# aepro_27C512.net
KiCad netlist of a schematic drawn in EAGLE
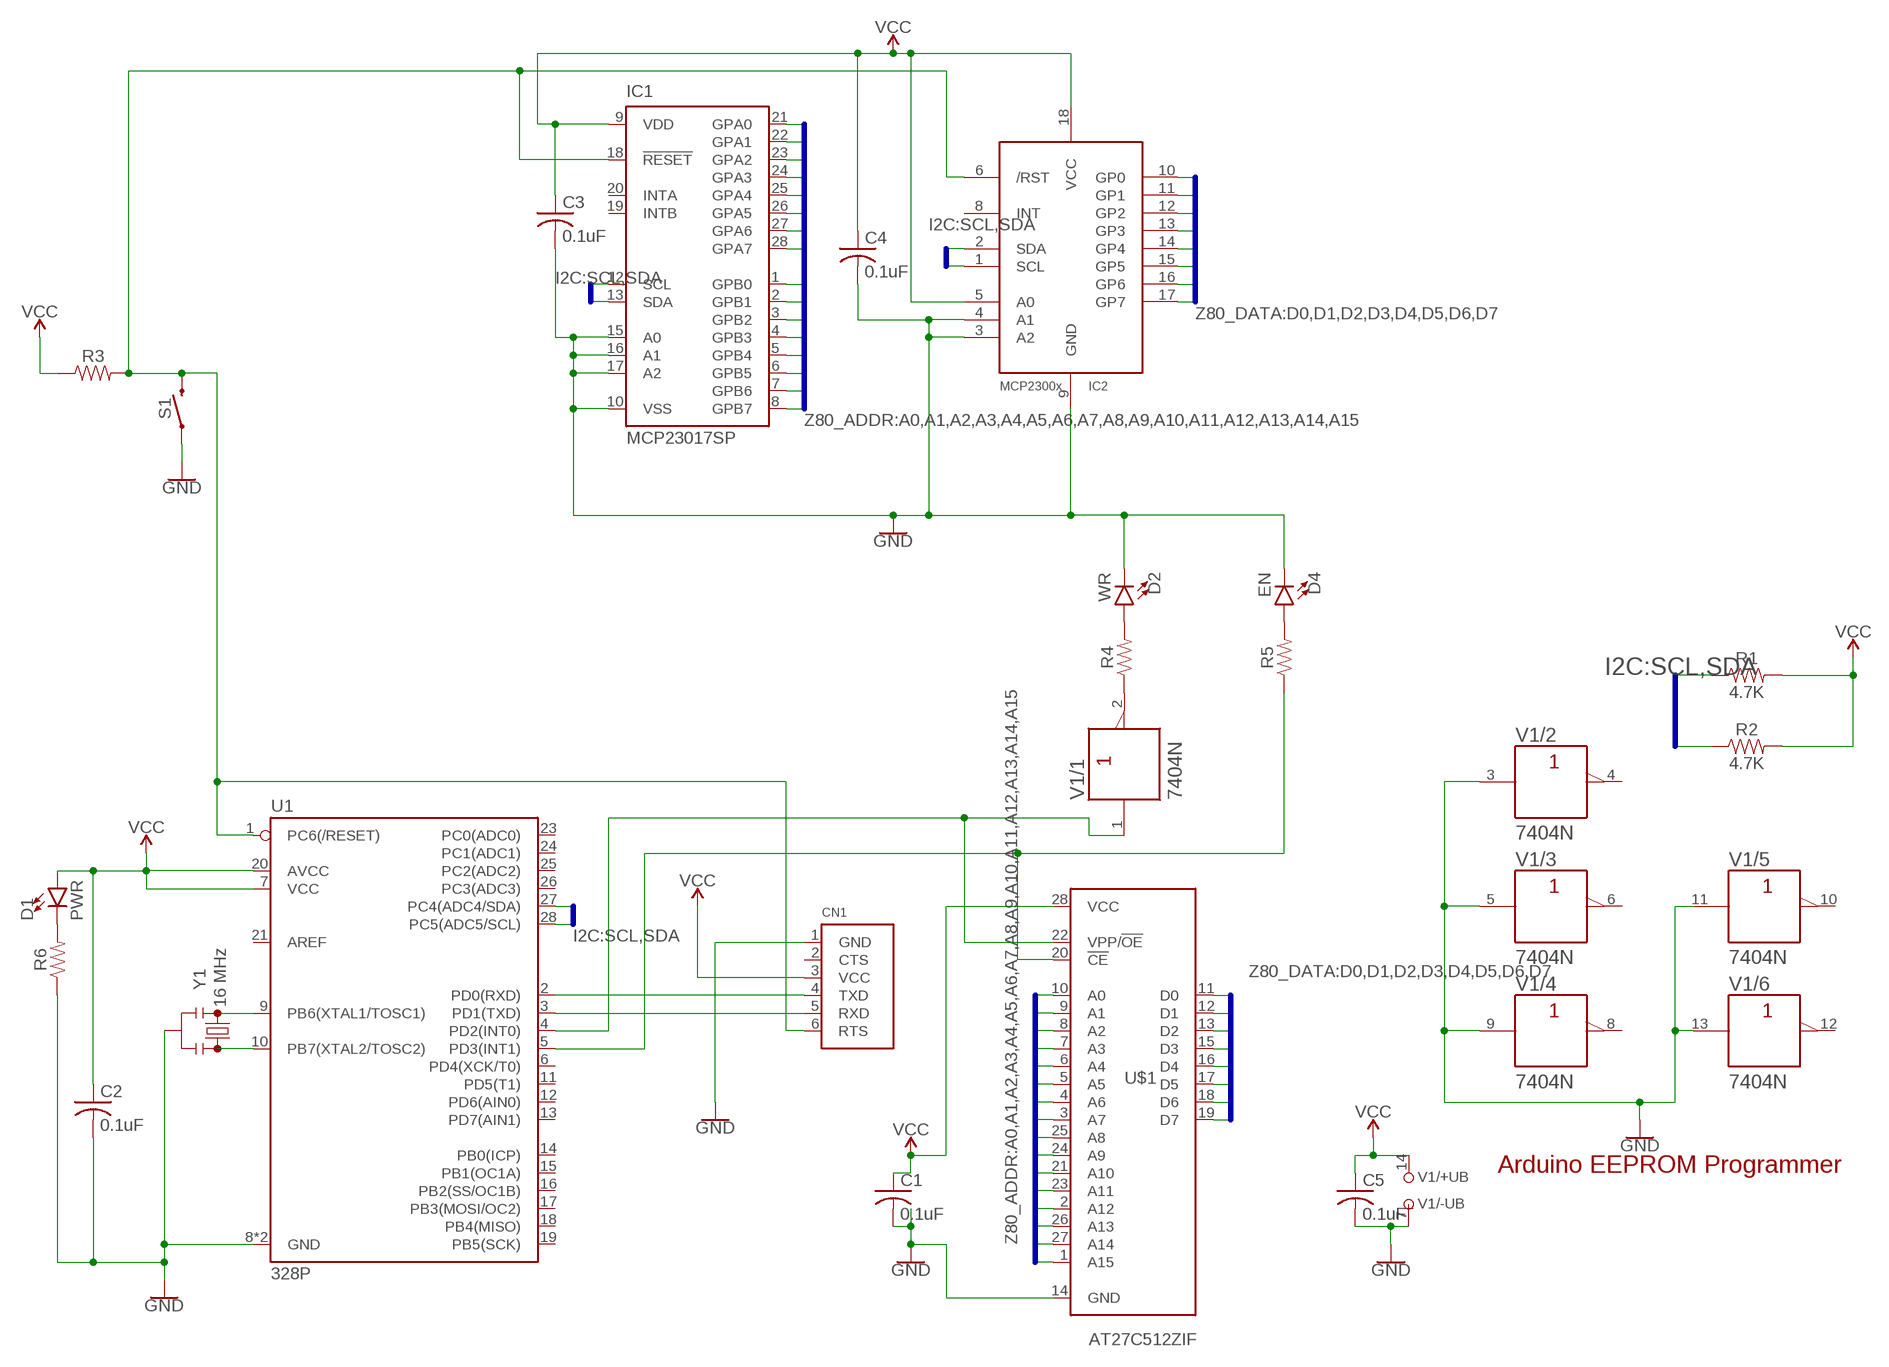
[diagram p0: schematic, sheet 1]

(export (version "E")
  (design (tool "Eeschema 10.0.6"))
  (components
    (comp (ref "C1")
      (value "0.1uF")
      (footprint "eagle-import:C050-024X044")
      (libsource (lib "eagle-import") (part "C-US050-024X044"))
    )
    (comp (ref "C2")
      (value "0.1uF")
      (footprint "eagle-import:C050-024X044")
      (libsource (lib "eagle-import") (part "C-US050-024X044"))
    )
    (comp (ref "C3")
      (value "0.1uF")
      (footprint "eagle-import:C050-024X044")
      (libsource (lib "eagle-import") (part "C-US050-024X044"))
    )
    (comp (ref "C4")
      (value "0.1uF")
      (footprint "eagle-import:C050-024X044")
      (libsource (lib "eagle-import") (part "C-US050-024X044"))
    )
    (comp (ref "C5")
      (value "0.1uF")
      (footprint "eagle-import:C050-024X044")
      (libsource (lib "eagle-import") (part "C-US050-024X044"))
    )
    (comp (ref "CN1")
      (value "FTDIUSBCABLE")
      (footprint "eagle-import:1X06_ROUND")
      (libsource (lib "eagle-import") (part "FTDIUSBCABLE"))
    )
    (comp (ref "D1")
      (value "PWR")
      (footprint "eagle-import:LED_3MM")
      (libsource (lib "eagle-import") (part "LED3MM"))
    )
    (comp (ref "D2")
      (value "WR")
      (footprint "eagle-import:LED_3MM")
      (libsource (lib "eagle-import") (part "LED3MM"))
    )
    (comp (ref "D4")
      (value "EN")
      (footprint "eagle-import:LED_3MM")
      (libsource (lib "eagle-import") (part "LED3MM"))
    )
    (comp (ref "IC1")
      (value "MCP23017SP")
      (footprint "eagle-import:DIL28-3")
      (libsource (lib "eagle-import") (part "MCP23017SP"))
    )
    (comp (ref "IC2")
      (value "MCP23008/P")
      (footprint "eagle-import:DIL18")
      (libsource (lib "eagle-import") (part "MCP23008/P"))
    )
    (comp (ref "R1")
      (value "4.7K")
      (footprint "eagle-import:AXIAL-0.3")
      (libsource (lib "eagle-import") (part "RESISTORAXIAL-0.3"))
    )
    (comp (ref "R2")
      (value "4.7K")
      (footprint "eagle-import:AXIAL-0.3")
      (libsource (lib "eagle-import") (part "RESISTORAXIAL-0.3"))
    )
    (comp (ref "R3")
      (value "RESISTORAXIAL-0.3")
      (footprint "eagle-import:AXIAL-0.3")
      (libsource (lib "eagle-import") (part "RESISTORAXIAL-0.3"))
    )
    (comp (ref "R4")
      (value "RESISTORAXIAL-0.3")
      (footprint "eagle-import:AXIAL-0.3")
      (libsource (lib "eagle-import") (part "RESISTORAXIAL-0.3"))
    )
    (comp (ref "R5")
      (value "RESISTORAXIAL-0.3")
      (footprint "eagle-import:AXIAL-0.3")
      (libsource (lib "eagle-import") (part "RESISTORAXIAL-0.3"))
    )
    (comp (ref "R6")
      (value "RESISTORAXIAL-0.3")
      (footprint "eagle-import:AXIAL-0.3")
      (libsource (lib "eagle-import") (part "RESISTORAXIAL-0.3"))
    )
    (comp (ref "S1")
      (value "MOMENTARY-SWITCH-SPST-PTH-6.0MM")
      (footprint "eagle-import:TACTILE_SWITCH_PTH_6.0MM")
      (libsource (lib "eagle-import") (part "MOMENTARY-SWITCH-SPST-PTH-6.0MM"))
    )
    (comp (ref "U$1")
      (value "AT27C512ZIF")
      (footprint "eagle-import:DIL28-6-ZIF_SOCKET")
      (libsource (lib "eagle-import") (part "AT27C512ZIF"))
    )
    (comp (ref "U1")
      (value "328P")
      (footprint "eagle-import:DIP28")
      (libsource (lib "eagle-import") (part "ATMEGA328P_PDIP"))
    )
    (comp (ref "V1")
      (value "7404N")
      (footprint "eagle-import:DIL14")
      (libsource (lib "eagle-import") (part "7404N"))
    )
    (comp (ref "Y1")
      (value "16 MHz")
      (footprint "eagle-import:RESONATOR-PTH-7.6X3.8")
      (libsource (lib "eagle-import") (part "RESONATORPTH-7.6X3.8"))
    )
  )
  (nets
    (net (code "4") (name "/A0") (class "Default")
      (node (ref "IC1") (pin "21") (pinfunction "GPA0_21") (pintype "bidirectional"))
      (node (ref "U$1") (pin "10") (pinfunction "A0_10") (pintype "input"))
    )
    (net (code "5") (name "/A1") (class "Default")
      (node (ref "IC1") (pin "22") (pinfunction "GPA1_22") (pintype "bidirectional"))
      (node (ref "U$1") (pin "9") (pinfunction "A1_9") (pintype "input"))
    )
    (net (code "6") (name "/A2") (class "Default")
      (node (ref "IC1") (pin "23") (pinfunction "GPA2_23") (pintype "bidirectional"))
      (node (ref "U$1") (pin "8") (pinfunction "A2_8") (pintype "input"))
    )
    (net (code "7") (name "/A3") (class "Default")
      (node (ref "IC1") (pin "24") (pinfunction "GPA3_24") (pintype "bidirectional"))
      (node (ref "U$1") (pin "7") (pinfunction "A3_7") (pintype "input"))
    )
    (net (code "8") (name "/A4") (class "Default")
      (node (ref "IC1") (pin "25") (pinfunction "GPA4_25") (pintype "bidirectional"))
      (node (ref "U$1") (pin "6") (pinfunction "A4_6") (pintype "input"))
    )
    (net (code "9") (name "/A5") (class "Default")
      (node (ref "IC1") (pin "26") (pinfunction "GPA5_26") (pintype "bidirectional"))
      (node (ref "U$1") (pin "5") (pinfunction "A5_5") (pintype "input"))
    )
    (net (code "10") (name "/A6") (class "Default")
      (node (ref "IC1") (pin "27") (pinfunction "GPA6_27") (pintype "bidirectional"))
      (node (ref "U$1") (pin "4") (pinfunction "A6_4") (pintype "input"))
    )
    (net (code "11") (name "/A7") (class "Default")
      (node (ref "IC1") (pin "28") (pinfunction "GPA7_28") (pintype "bidirectional"))
      (node (ref "U$1") (pin "3") (pinfunction "A7_3") (pintype "input"))
    )
    (net (code "12") (name "/A8") (class "Default")
      (node (ref "IC1") (pin "1") (pinfunction "GPB0_1") (pintype "bidirectional"))
      (node (ref "U$1") (pin "25") (pinfunction "A8_25") (pintype "input"))
    )
    (net (code "13") (name "/A9") (class "Default")
      (node (ref "IC1") (pin "2") (pinfunction "GPB1_2") (pintype "bidirectional"))
      (node (ref "U$1") (pin "24") (pinfunction "A9_24") (pintype "input"))
    )
    (net (code "14") (name "/A10") (class "Default")
      (node (ref "IC1") (pin "3") (pinfunction "GPB2_3") (pintype "bidirectional"))
      (node (ref "U$1") (pin "21") (pinfunction "A10_21") (pintype "input"))
    )
    (net (code "15") (name "/A11") (class "Default")
      (node (ref "IC1") (pin "4") (pinfunction "GPB3_4") (pintype "bidirectional"))
      (node (ref "U$1") (pin "23") (pinfunction "A11_23") (pintype "input"))
    )
    (net (code "16") (name "/A12") (class "Default")
      (node (ref "IC1") (pin "5") (pinfunction "GPB4_5") (pintype "bidirectional"))
      (node (ref "U$1") (pin "2") (pinfunction "A12_2") (pintype "input"))
    )
    (net (code "17") (name "/A13") (class "Default")
      (node (ref "IC1") (pin "6") (pinfunction "GPB5_6") (pintype "bidirectional"))
      (node (ref "U$1") (pin "26") (pinfunction "A13_26") (pintype "input"))
    )
    (net (code "18") (name "/A14") (class "Default")
      (node (ref "IC1") (pin "7") (pinfunction "GPB6_7") (pintype "bidirectional"))
      (node (ref "U$1") (pin "27") (pinfunction "A14_27") (pintype "input"))
    )
    (net (code "19") (name "/A15") (class "Default")
      (node (ref "IC1") (pin "8") (pinfunction "GPB7_8") (pintype "bidirectional"))
      (node (ref "U$1") (pin "1") (pinfunction "A15_1") (pintype "input"))
    )
    (net (code "20") (name "/D1") (class "Default")
      (node (ref "IC2") (pin "11") (pinfunction "GP1_11") (pintype "bidirectional"))
      (node (ref "U$1") (pin "12") (pinfunction "D1_12") (pintype "tri_state"))
    )
    (net (code "21") (name "/D2") (class "Default")
      (node (ref "IC2") (pin "12") (pinfunction "GP2_12") (pintype "bidirectional"))
      (node (ref "U$1") (pin "13") (pinfunction "D2_13") (pintype "tri_state"))
    )
    (net (code "22") (name "/D3") (class "Default")
      (node (ref "IC2") (pin "13") (pinfunction "GP3_13") (pintype "bidirectional"))
      (node (ref "U$1") (pin "15") (pinfunction "D3_15") (pintype "tri_state"))
    )
    (net (code "23") (name "/D4") (class "Default")
      (node (ref "IC2") (pin "14") (pinfunction "GP4_14") (pintype "bidirectional"))
      (node (ref "U$1") (pin "16") (pinfunction "D4_16") (pintype "tri_state"))
    )
    (net (code "24") (name "/D5") (class "Default")
      (node (ref "IC2") (pin "15") (pinfunction "GP5_15") (pintype "bidirectional"))
      (node (ref "U$1") (pin "17") (pinfunction "D5_17") (pintype "tri_state"))
    )
    (net (code "25") (name "/D6") (class "Default")
      (node (ref "IC2") (pin "16") (pinfunction "GP6_16") (pintype "bidirectional"))
      (node (ref "U$1") (pin "18") (pinfunction "D6_18") (pintype "tri_state"))
    )
    (net (code "26") (name "/D7") (class "Default")
      (node (ref "IC2") (pin "17") (pinfunction "GP7_17") (pintype "bidirectional"))
      (node (ref "U$1") (pin "19") (pinfunction "D7_19") (pintype "tri_state"))
    )
    (net (code "27") (name "/I2C:SCL") (class "Default")
      (node (ref "IC1") (pin "12") (pinfunction "SCL_12") (pintype "input"))
      (node (ref "IC2") (pin "1") (pinfunction "SCL_1") (pintype "bidirectional"))
      (node (ref "R1") (pin "P$1") (pinfunction "1_P$1") (pintype "passive"))
      (node (ref "U1") (pin "28") (pinfunction "PC5(ADC5/SCL)_28") (pintype "bidirectional"))
    )
    (net (code "28") (name "/SDA") (class "Default")
      (node (ref "IC1") (pin "13") (pinfunction "SDA_13") (pintype "bidirectional"))
      (node (ref "IC2") (pin "2") (pinfunction "SDA_2") (pintype "bidirectional"))
      (node (ref "R2") (pin "P$1") (pinfunction "1_P$1") (pintype "passive"))
      (node (ref "U1") (pin "27") (pinfunction "PC4(ADC4/SDA)_27") (pintype "bidirectional"))
    )
    (net (code "29") (name "/Z80_DATA:D0") (class "Default")
      (node (ref "IC2") (pin "10") (pinfunction "GP0_10") (pintype "bidirectional"))
      (node (ref "U$1") (pin "11") (pinfunction "D0_11") (pintype "tri_state"))
    )
    (net (code "33") (name "GND") (class "Default")
      (node (ref "C1") (pin "2") (pinfunction "2_2") (pintype "passive"))
      (node (ref "C2") (pin "2") (pinfunction "2_2") (pintype "passive"))
      (node (ref "C3") (pin "2") (pinfunction "2_2") (pintype "passive"))
      (node (ref "C4") (pin "2") (pinfunction "2_2") (pintype "passive"))
      (node (ref "C5") (pin "2") (pinfunction "2_2") (pintype "passive"))
      (node (ref "CN1") (pin "1") (pinfunction "GND_1") (pintype "bidirectional"))
      (node (ref "D2") (pin "K") (pinfunction "C_K") (pintype "passive"))
      (node (ref "D4") (pin "K") (pinfunction "C_K") (pintype "passive"))
      (node (ref "IC1") (pin "10") (pinfunction "VSS_10") (pintype "power_in"))
      (node (ref "IC1") (pin "15") (pinfunction "A0_15") (pintype "input"))
      (node (ref "IC1") (pin "16") (pinfunction "A1_16") (pintype "input"))
      (node (ref "IC1") (pin "17") (pinfunction "A2_17") (pintype "input"))
      (node (ref "IC2") (pin "3") (pinfunction "A2_3") (pintype "input"))
      (node (ref "IC2") (pin "4") (pinfunction "A1_4") (pintype "input"))
      (node (ref "IC2") (pin "9") (pinfunction "GND_9") (pintype "power_in"))
      (node (ref "R6") (pin "P$1") (pinfunction "1_P$1") (pintype "passive"))
      (node (ref "S1") (pin "1") (pinfunction "1_1") (pintype "passive"))
      (node (ref "U$1") (pin "14") (pinfunction "GND_14") (pintype "power_in"))
      (node (ref "U1") (pin "22") (pinfunction "GND_22") (pintype "bidirectional"))
      (node (ref "U1") (pin "8") (pinfunction "GND_8") (pintype "bidirectional"))
      (node (ref "V1") (pin "11") (pinfunction "A_11") (pintype "input"))
      (node (ref "V1") (pin "13") (pinfunction "A_13") (pintype "input"))
      (node (ref "V1") (pin "3") (pinfunction "A_3") (pintype "input"))
      (node (ref "V1") (pin "5") (pinfunction "A_5") (pintype "input"))
      (node (ref "V1") (pin "7") (pinfunction "-UB_7") (pintype "power_in"))
      (node (ref "V1") (pin "9") (pinfunction "A_9") (pintype "input"))
      (node (ref "Y1") (pin "2") (pinfunction "2_2") (pintype "passive"))
    )
    (net (code "34") (name "Net-(CN1-RTS)") (class "Default")
      (node (ref "CN1") (pin "6") (pinfunction "RTS_6") (pintype "bidirectional"))
      (node (ref "IC1") (pin "18") (pinfunction "~{RESET}_18") (pintype "input"))
      (node (ref "IC2") (pin "6") (pinfunction "/RST_6") (pintype "input"))
      (node (ref "R3") (pin "P$2") (pinfunction "2_P$2") (pintype "passive"))
      (node (ref "S1") (pin "3") (pinfunction "2_3") (pintype "passive"))
      (node (ref "U1") (pin "1") (pinfunction "PC6(/RESET)_1") (pintype "bidirectional"))
    )
    (net (code "35") (name "Net-(CN1-RXD)") (class "Default")
      (node (ref "CN1") (pin "5") (pinfunction "RXD_5") (pintype "bidirectional"))
      (node (ref "U1") (pin "3") (pinfunction "PD1(TXD)_3") (pintype "bidirectional"))
    )
    (net (code "36") (name "Net-(CN1-TXD)") (class "Default")
      (node (ref "CN1") (pin "4") (pinfunction "TXD_4") (pintype "bidirectional"))
      (node (ref "U1") (pin "2") (pinfunction "PD0(RXD)_2") (pintype "bidirectional"))
    )
    (net (code "37") (name "Net-(D1-C)") (class "Default")
      (node (ref "D1") (pin "K") (pinfunction "C_K") (pintype "passive"))
      (node (ref "R6") (pin "P$2") (pinfunction "2_P$2") (pintype "passive"))
    )
    (net (code "38") (name "Net-(R4-1)") (class "Default")
      (node (ref "R4") (pin "P$1") (pinfunction "1_P$1") (pintype "passive"))
      (node (ref "V1") (pin "2") (pinfunction "Y_2") (pintype "output"))
    )
    (net (code "39") (name "Net-(R4-2)") (class "Default")
      (node (ref "D2") (pin "A") (pinfunction "A_A") (pintype "passive"))
      (node (ref "R4") (pin "P$2") (pinfunction "2_P$2") (pintype "passive"))
    )
    (net (code "40") (name "Net-(R5-1)") (class "Default")
      (node (ref "R5") (pin "P$1") (pinfunction "1_P$1") (pintype "passive"))
      (node (ref "U$1") (pin "20") (pinfunction "~{CE}_20") (pintype "input"))
      (node (ref "U1") (pin "5") (pinfunction "PD3(INT1)_5") (pintype "bidirectional"))
    )
    (net (code "41") (name "Net-(R5-2)") (class "Default")
      (node (ref "D4") (pin "A") (pinfunction "A_A") (pintype "passive"))
      (node (ref "R5") (pin "P$2") (pinfunction "2_P$2") (pintype "passive"))
    )
    (net (code "42") (name "Net-(U$1-VPP{slash}~{OE})") (class "Default")
      (node (ref "U$1") (pin "22") (pinfunction "VPP/~{OE}_22") (pintype "input"))
      (node (ref "U1") (pin "4") (pinfunction "PD2(INT0)_4") (pintype "bidirectional"))
      (node (ref "V1") (pin "1") (pinfunction "A_1") (pintype "input"))
    )
    (net (code "43") (name "Net-(U1-PB6(XTAL1{slash}TOSC1))") (class "Default")
      (node (ref "U1") (pin "9") (pinfunction "PB6(XTAL1/TOSC1)_9") (pintype "bidirectional"))
      (node (ref "Y1") (pin "1") (pinfunction "1_1") (pintype "passive"))
    )
    (net (code "44") (name "Net-(U1-PB7(XTAL2{slash}TOSC2))") (class "Default")
      (node (ref "U1") (pin "10") (pinfunction "PB7(XTAL2/TOSC2)_10") (pintype "bidirectional"))
      (node (ref "Y1") (pin "3") (pinfunction "3_3") (pintype "passive"))
    )
    (net (code "45") (name "VCC") (class "Default")
      (node (ref "C1") (pin "1") (pinfunction "1_1") (pintype "passive"))
      (node (ref "C2") (pin "1") (pinfunction "1_1") (pintype "passive"))
      (node (ref "C3") (pin "1") (pinfunction "1_1") (pintype "passive"))
      (node (ref "C4") (pin "1") (pinfunction "1_1") (pintype "passive"))
      (node (ref "C5") (pin "1") (pinfunction "1_1") (pintype "passive"))
      (node (ref "CN1") (pin "3") (pinfunction "VCC_3") (pintype "bidirectional"))
      (node (ref "D1") (pin "A") (pinfunction "A_A") (pintype "passive"))
      (node (ref "IC1") (pin "9") (pinfunction "VDD_9") (pintype "power_in"))
      (node (ref "IC2") (pin "18") (pinfunction "VCC_18") (pintype "power_in"))
      (node (ref "IC2") (pin "5") (pinfunction "A0_5") (pintype "input"))
      (node (ref "R1") (pin "P$2") (pinfunction "2_P$2") (pintype "passive"))
      (node (ref "R2") (pin "P$2") (pinfunction "2_P$2") (pintype "passive"))
      (node (ref "R3") (pin "P$1") (pinfunction "1_P$1") (pintype "passive"))
      (node (ref "U$1") (pin "28") (pinfunction "VCC_28") (pintype "power_in"))
      (node (ref "U1") (pin "20") (pinfunction "AVCC_20") (pintype "bidirectional"))
      (node (ref "U1") (pin "7") (pinfunction "VCC_7") (pintype "bidirectional"))
      (node (ref "V1") (pin "14") (pinfunction "+UB_14") (pintype "power_in"))
    )
    (net (code "46") (name "unconnected-(CN1-CTS-Pad2)") (class "Default")
      (node (ref "CN1") (pin "2") (pinfunction "CTS_2") (pintype "bidirectional"))
    )
    (net (code "47") (name "unconnected-(IC1-INTA-Pad20)") (class "Default")
      (node (ref "IC1") (pin "20") (pinfunction "INTA_20") (pintype "output"))
    )
    (net (code "48") (name "unconnected-(IC1-INTB-Pad19)") (class "Default")
      (node (ref "IC1") (pin "19") (pinfunction "INTB_19") (pintype "output"))
    )
    (net (code "49") (name "unconnected-(IC2-INT-Pad8)") (class "Default")
      (node (ref "IC2") (pin "8") (pinfunction "INT_8") (pintype "output"))
    )
    (net (code "50") (name "unconnected-(U1-AREF-Pad21)") (class "Default")
      (node (ref "U1") (pin "21") (pinfunction "AREF_21") (pintype "bidirectional"))
    )
    (net (code "51") (name "unconnected-(U1-PB0(ICP)-Pad14)") (class "Default")
      (node (ref "U1") (pin "14") (pinfunction "PB0(ICP)_14") (pintype "bidirectional"))
    )
    (net (code "52") (name "unconnected-(U1-PB1(OC1A)-Pad15)") (class "Default")
      (node (ref "U1") (pin "15") (pinfunction "PB1(OC1A)_15") (pintype "bidirectional"))
    )
    (net (code "53") (name "unconnected-(U1-PB2(SS{slash}OC1B)-Pad16)") (class "Default")
      (node (ref "U1") (pin "16") (pinfunction "PB2(SS/OC1B)_16") (pintype "bidirectional"))
    )
    (net (code "54") (name "unconnected-(U1-PB3(MOSI{slash}OC2)-Pad17)") (class "Default")
      (node (ref "U1") (pin "17") (pinfunction "PB3(MOSI/OC2)_17") (pintype "bidirectional"))
    )
    (net (code "55") (name "unconnected-(U1-PB4(MISO)-Pad18)") (class "Default")
      (node (ref "U1") (pin "18") (pinfunction "PB4(MISO)_18") (pintype "bidirectional"))
    )
    (net (code "56") (name "unconnected-(U1-PB5(SCK)-Pad19)") (class "Default")
      (node (ref "U1") (pin "19") (pinfunction "PB5(SCK)_19") (pintype "bidirectional"))
    )
    (net (code "57") (name "unconnected-(U1-PC0(ADC0)-Pad23)") (class "Default")
      (node (ref "U1") (pin "23") (pinfunction "PC0(ADC0)_23") (pintype "bidirectional"))
    )
    (net (code "58") (name "unconnected-(U1-PC1(ADC1)-Pad24)") (class "Default")
      (node (ref "U1") (pin "24") (pinfunction "PC1(ADC1)_24") (pintype "bidirectional"))
    )
    (net (code "59") (name "unconnected-(U1-PC2(ADC2)-Pad25)") (class "Default")
      (node (ref "U1") (pin "25") (pinfunction "PC2(ADC2)_25") (pintype "bidirectional"))
    )
    (net (code "60") (name "unconnected-(U1-PC3(ADC3)-Pad26)") (class "Default")
      (node (ref "U1") (pin "26") (pinfunction "PC3(ADC3)_26") (pintype "bidirectional"))
    )
    (net (code "61") (name "unconnected-(U1-PD4(XCK{slash}T0)-Pad6)") (class "Default")
      (node (ref "U1") (pin "6") (pinfunction "PD4(XCK/T0)_6") (pintype "bidirectional"))
    )
    (net (code "62") (name "unconnected-(U1-PD5(T1)-Pad11)") (class "Default")
      (node (ref "U1") (pin "11") (pinfunction "PD5(T1)_11") (pintype "bidirectional"))
    )
    (net (code "63") (name "unconnected-(U1-PD6(AIN0)-Pad12)") (class "Default")
      (node (ref "U1") (pin "12") (pinfunction "PD6(AIN0)_12") (pintype "bidirectional"))
    )
    (net (code "64") (name "unconnected-(U1-PD7(AIN1)-Pad13)") (class "Default")
      (node (ref "U1") (pin "13") (pinfunction "PD7(AIN1)_13") (pintype "bidirectional"))
    )
    (net (code "65") (name "unconnected-(V1D-Y-Pad4)") (class "Default")
      (node (ref "V1") (pin "4") (pinfunction "Y_4") (pintype "output"))
    )
    (net (code "66") (name "unconnected-(V1E-Y-Pad6)") (class "Default")
      (node (ref "V1") (pin "6") (pinfunction "Y_6") (pintype "output"))
    )
    (net (code "67") (name "unconnected-(V1F-Y-Pad8)") (class "Default")
      (node (ref "V1") (pin "8") (pinfunction "Y_8") (pintype "output"))
    )
    (net (code "68") (name "unconnected-(V1G-Y-Pad10)") (class "Default")
      (node (ref "V1") (pin "10") (pinfunction "Y_10") (pintype "output"))
    )
    (net (code "69") (name "unconnected-(V1H-Y-Pad12)") (class "Default")
      (node (ref "V1") (pin "12") (pinfunction "Y_12") (pintype "output"))
    )
  )
)
